# ETHERNET.net
KiCad netlist of a schematic drawn in Altium Designer
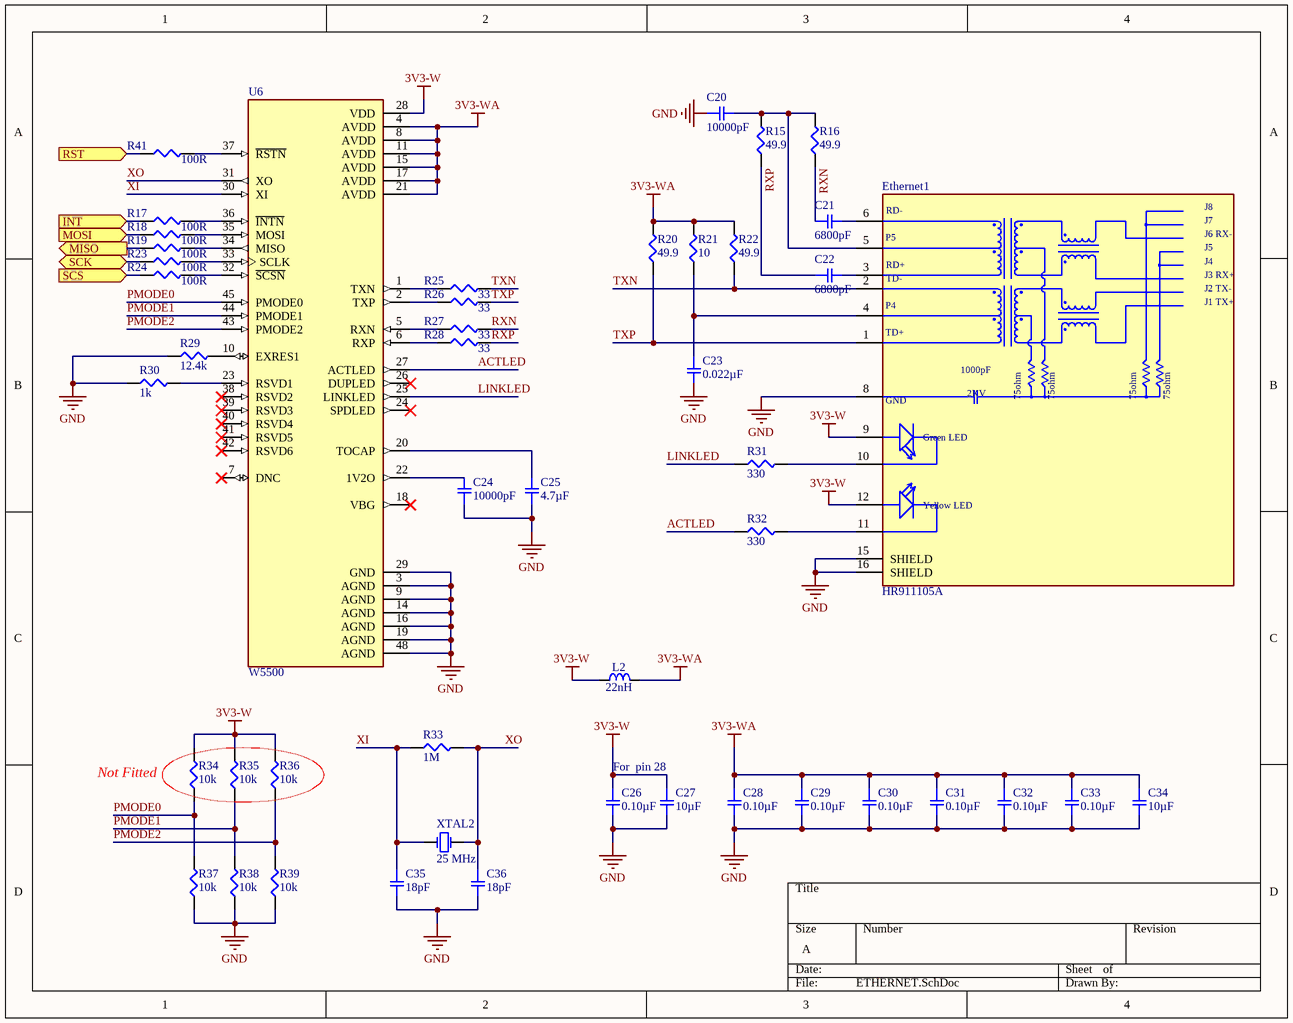
[diagram p0: ETHERNET.SchDoc]

(export (version "E")
  (design (tool "Eeschema 10.0.6"))
  (components
    (comp (ref "C20")
      (value "10000pF")
      (footprint "0805")
      (description "CAP CER 10000PF 250V X7T 0805")
      (fields
        (field (name "DIGI-KEY PART NUMBER") "490-13986-1-ND")
        (field (name "PART NUMBER") "GC321AD72E103KX01D")
      )
      (libsource (lib "Cap_805") (part "GC321AD72E103KX01D"))
    )
    (comp (ref "C21")
      (value "6800pF")
      (footprint "0805")
      (description "CAP CER 6800PF 50V X7R 0805")
      (fields
        (field (name "DIGI-KEY PART NUMBER") "490-5853-1-ND")
        (field (name "PART NUMBER") "GCJ216R71H682KA01D")
      )
      (libsource (lib "Cap_805") (part "GCJ216R71H682KA01D"))
    )
    (comp (ref "C22")
      (value "6800pF")
      (footprint "0805")
      (description "CAP CER 6800PF 50V X7R 0805")
      (fields
        (field (name "DIGI-KEY PART NUMBER") "490-5853-1-ND")
        (field (name "PART NUMBER") "GCJ216R71H682KA01D")
      )
      (libsource (lib "Cap_805") (part "GCJ216R71H682KA01D"))
    )
    (comp (ref "C23")
      (value "0.022µF")
      (footprint "0805")
      (description "CAP CER 0.022UF 50V X7R 0805")
      (fields
        (field (name "DIGI-KEY PART NUMBER") "490-5842-1-ND")
        (field (name "PART NUMBER") "GCJ216R71H223KA01D")
      )
      (libsource (lib "Cap_805") (part "GCJ216R71H223KA01D"))
    )
    (comp (ref "C24")
      (value "10000pF")
      (footprint "0805")
      (description "CAP CER 10000PF 250V X7T 0805")
      (fields
        (field (name "DIGI-KEY PART NUMBER") "490-13986-1-ND")
        (field (name "PART NUMBER") "GC321AD72E103KX01D")
      )
      (libsource (lib "Cap_805") (part "GC321AD72E103KX01D"))
    )
    (comp (ref "C25")
      (value "4.7µF")
      (footprint "0805")
      (description "CAP CER 4.7UF 10V X7S 0805")
      (fields
        (field (name "DIGI-KEY PART NUMBER") "490-6062-1-ND")
        (field (name "PART NUMBER") "GCM21BC71A475KA73L")
      )
      (libsource (lib "Cap_805") (part "GCM21BC71A475KA73L"))
    )
    (comp (ref "C26")
      (value "0.10µF")
      (footprint "0805")
      (description "CAP CER 0.1UF 25V X7R 0805")
      (fields
        (field (name "DIGI-KEY PART NUMBER") "490-12754-1-ND")
        (field (name "PART NUMBER") "GRM219R71E104KA01D")
      )
      (libsource (lib "Cap_805") (part "GRM219R71E104KA01D"))
    )
    (comp (ref "C27")
      (value "10µF")
      (footprint "0805")
      (description "CAP CER 10UF 10V X7R 0805")
      (fields
        (field (name "DIGI-KEY PART NUMBER") "490-12646-1-ND")
        (field (name "PART NUMBER") "GCJ21BR71A106KE01L")
      )
      (libsource (lib "Cap_805") (part "GCJ21BR71A106KE01L"))
    )
    (comp (ref "C28")
      (value "0.10µF")
      (footprint "0805")
      (description "CAP CER 0.1UF 25V X7R 0805")
      (fields
        (field (name "DIGI-KEY PART NUMBER") "490-12754-1-ND")
        (field (name "PART NUMBER") "GRM219R71E104KA01D")
      )
      (libsource (lib "Cap_805") (part "GRM219R71E104KA01D"))
    )
    (comp (ref "C29")
      (value "0.10µF")
      (footprint "0805")
      (description "CAP CER 0.1UF 25V X7R 0805")
      (fields
        (field (name "DIGI-KEY PART NUMBER") "490-12754-1-ND")
        (field (name "PART NUMBER") "GRM219R71E104KA01D")
      )
      (libsource (lib "Cap_805") (part "GRM219R71E104KA01D"))
    )
    (comp (ref "C30")
      (value "0.10µF")
      (footprint "0805")
      (description "CAP CER 0.1UF 25V X7R 0805")
      (fields
        (field (name "DIGI-KEY PART NUMBER") "490-12754-1-ND")
        (field (name "PART NUMBER") "GRM219R71E104KA01D")
      )
      (libsource (lib "Cap_805") (part "GRM219R71E104KA01D"))
    )
    (comp (ref "C31")
      (value "0.10µF")
      (footprint "0805")
      (description "CAP CER 0.1UF 25V X7R 0805")
      (fields
        (field (name "DIGI-KEY PART NUMBER") "490-12754-1-ND")
        (field (name "PART NUMBER") "GRM219R71E104KA01D")
      )
      (libsource (lib "Cap_805") (part "GRM219R71E104KA01D"))
    )
    (comp (ref "C32")
      (value "0.10µF")
      (footprint "0805")
      (description "CAP CER 0.1UF 25V X7R 0805")
      (fields
        (field (name "DIGI-KEY PART NUMBER") "490-12754-1-ND")
        (field (name "PART NUMBER") "GRM219R71E104KA01D")
      )
      (libsource (lib "Cap_805") (part "GRM219R71E104KA01D"))
    )
    (comp (ref "C33")
      (value "0.10µF")
      (footprint "0805")
      (description "CAP CER 0.1UF 25V X7R 0805")
      (fields
        (field (name "DIGI-KEY PART NUMBER") "490-12754-1-ND")
        (field (name "PART NUMBER") "GRM219R71E104KA01D")
      )
      (libsource (lib "Cap_805") (part "GRM219R71E104KA01D"))
    )
    (comp (ref "C34")
      (value "10µF")
      (footprint "0805")
      (description "CAP CER 10UF 10V X7R 0805")
      (fields
        (field (name "DIGI-KEY PART NUMBER") "490-12646-1-ND")
        (field (name "PART NUMBER") "GCJ21BR71A106KE01L")
      )
      (libsource (lib "Cap_805") (part "GCJ21BR71A106KE01L"))
    )
    (comp (ref "C35")
      (value "18pF")
      (footprint "0805")
      (description "CAP CER 18PF 100V NP0 0805")
      (fields
        (field (name "DIGI-KEY PART NUMBER") "490-3606-1-ND")
        (field (name "PART NUMBER") "GQM2195C2A180JB01D")
      )
      (libsource (lib "Cap_805") (part "GQM2195C2A180JB01D"))
    )
    (comp (ref "C36")
      (value "18pF")
      (footprint "0805")
      (description "CAP CER 18PF 100V NP0 0805")
      (fields
        (field (name "DIGI-KEY PART NUMBER") "490-3606-1-ND")
        (field (name "PART NUMBER") "GQM2195C2A180JB01D")
      )
      (libsource (lib "Cap_805") (part "GQM2195C2A180JB01D"))
    )
    (comp (ref "Ethernet1")
      (value "HR911105A")
      (footprint "HANRUN_HR911105A")
      (description "HR911105A Ethernet Interface Arduino Platform Evaluation Expansion Board")
      (fields (field (name "MF") "DFRobot"))
      (libsource (lib "RJ45 Ethernet Connector HR911105A") (part "HR911105A"))
    )
    (comp (ref "L2")
      (value "22nH")
      (footprint "0805")
      (description "Inductor")
      (fields
        (field (name "PART NUMBER") "IND0805_WURTH_742792022")
        (field (name "POWER") "2A")
        (field (name "AUTHOR") "CERN DEM JLC")
      )
      (libsource (lib "Inductors SMD") (part "IND0805_WURTH_742792022"))
    )
    (comp (ref "R15")
      (value "49.9")
      (footprint "0805")
      (description "RES SMD 49.9 OHM 1% 1/8W 0805")
      (fields
        (field (name "PART NUMBER") "ERJ-6ENF49R9V")
        (field (name "DIGI-KEY PART NUMBER") "P49.9CCT-ND")
      )
      (libsource (lib "Res_805") (part "ERJ-6ENF49R9V"))
    )
    (comp (ref "R16")
      (value "49.9")
      (footprint "0805")
      (description "RES SMD 49.9 OHM 1% 1/8W 0805")
      (fields
        (field (name "PART NUMBER") "ERJ-6ENF49R9V")
        (field (name "DIGI-KEY PART NUMBER") "P49.9CCT-ND")
      )
      (libsource (lib "Res_805") (part "ERJ-6ENF49R9V"))
    )
    (comp (ref "R17")
      (value "100R")
      (footprint "0805")
      (description "RES SMD 33 OHM 1% 1/8W 0805")
      (fields
        (field (name "PART NUMBER") "ERJ-6ENF33R0V")
        (field (name "DIGI-KEY PART NUMBER") "P33.0CCT-ND")
      )
      (libsource (lib "Res_805") (part "ERJ-6ENF33R0V"))
    )
    (comp (ref "R18")
      (value "100R")
      (footprint "0805")
      (description "RES SMD 33 OHM 1% 1/8W 0805")
      (fields
        (field (name "PART NUMBER") "ERJ-6ENF33R0V")
        (field (name "DIGI-KEY PART NUMBER") "P33.0CCT-ND")
      )
      (libsource (lib "Res_805") (part "ERJ-6ENF33R0V"))
    )
    (comp (ref "R19")
      (value "100R")
      (footprint "0805")
      (description "RES SMD 33 OHM 1% 1/8W 0805")
      (fields
        (field (name "PART NUMBER") "ERJ-6ENF33R0V")
        (field (name "DIGI-KEY PART NUMBER") "P33.0CCT-ND")
      )
      (libsource (lib "Res_805") (part "ERJ-6ENF33R0V"))
    )
    (comp (ref "R20")
      (value "49.9")
      (footprint "0805")
      (description "RES SMD 49.9 OHM 1% 1/8W 0805")
      (fields
        (field (name "PART NUMBER") "ERJ-6ENF49R9V")
        (field (name "DIGI-KEY PART NUMBER") "P49.9CCT-ND")
      )
      (libsource (lib "Res_805") (part "ERJ-6ENF49R9V"))
    )
    (comp (ref "R21")
      (value "10")
      (footprint "0805")
      (description "RES SMD 10 OHM 1% 1/8W 0805")
      (fields
        (field (name "PART NUMBER") "ERJ-6ENF10R0V")
        (field (name "DIGI-KEY PART NUMBER") "P10.0CCT-ND")
      )
      (libsource (lib "Res_805") (part "ERJ-6ENF10R0V"))
    )
    (comp (ref "R22")
      (value "49.9")
      (footprint "0805")
      (description "RES SMD 49.9 OHM 1% 1/8W 0805")
      (fields
        (field (name "PART NUMBER") "ERJ-6ENF49R9V")
        (field (name "DIGI-KEY PART NUMBER") "P49.9CCT-ND")
      )
      (libsource (lib "Res_805") (part "ERJ-6ENF49R9V"))
    )
    (comp (ref "R23")
      (value "100R")
      (footprint "0805")
      (description "RES SMD 33 OHM 1% 1/8W 0805")
      (fields
        (field (name "PART NUMBER") "ERJ-6ENF33R0V")
        (field (name "DIGI-KEY PART NUMBER") "P33.0CCT-ND")
      )
      (libsource (lib "Res_805") (part "ERJ-6ENF33R0V"))
    )
    (comp (ref "R24")
      (value "100R")
      (footprint "0805")
      (description "RES SMD 33 OHM 1% 1/8W 0805")
      (fields
        (field (name "PART NUMBER") "ERJ-6ENF33R0V")
        (field (name "DIGI-KEY PART NUMBER") "P33.0CCT-ND")
      )
      (libsource (lib "Res_805") (part "ERJ-6ENF33R0V"))
    )
    (comp (ref "R25")
      (value "33")
      (footprint "0805")
      (description "RES SMD 33 OHM 1% 1/8W 0805")
      (fields
        (field (name "PART NUMBER") "ERJ-6ENF33R0V")
        (field (name "DIGI-KEY PART NUMBER") "P33.0CCT-ND")
      )
      (libsource (lib "Res_805") (part "ERJ-6ENF33R0V"))
    )
    (comp (ref "R26")
      (value "33")
      (footprint "0805")
      (description "RES SMD 33 OHM 1% 1/8W 0805")
      (fields
        (field (name "PART NUMBER") "ERJ-6ENF33R0V")
        (field (name "DIGI-KEY PART NUMBER") "P33.0CCT-ND")
      )
      (libsource (lib "Res_805") (part "ERJ-6ENF33R0V"))
    )
    (comp (ref "R27")
      (value "33")
      (footprint "0805")
      (description "RES SMD 33 OHM 1% 1/8W 0805")
      (fields
        (field (name "PART NUMBER") "ERJ-6ENF33R0V")
        (field (name "DIGI-KEY PART NUMBER") "P33.0CCT-ND")
      )
      (libsource (lib "Res_805") (part "ERJ-6ENF33R0V"))
    )
    (comp (ref "R28")
      (value "33")
      (footprint "0805")
      (description "RES SMD 33 OHM 1% 1/8W 0805")
      (fields
        (field (name "PART NUMBER") "ERJ-6ENF33R0V")
        (field (name "DIGI-KEY PART NUMBER") "P33.0CCT-ND")
      )
      (libsource (lib "Res_805") (part "ERJ-6ENF33R0V"))
    )
    (comp (ref "R29")
      (value "12.4k")
      (footprint "0805")
      (description "RES SMD 12.4K OHM 1% 1/8W 0805")
      (fields
        (field (name "PART NUMBER") "ERJ-6ENF1242V")
        (field (name "DIGI-KEY PART NUMBER") "P12.4KCCT-ND")
      )
      (libsource (lib "Res_805") (part "ERJ-6ENF1242V"))
    )
    (comp (ref "R30")
      (value "1k")
      (footprint "0805")
      (description "RES SMD 1K OHM 1% 1/8W 0805")
      (fields
        (field (name "PART NUMBER") "ERJ-6ENF1001V")
        (field (name "DIGI-KEY PART NUMBER") "P1.00KCCT-ND")
      )
      (libsource (lib "Res_805") (part "ERJ-6ENF1001V"))
    )
    (comp (ref "R31")
      (value "330")
      (footprint "0805")
      (description "RES SMD 330 OHM 5% 1/8W 0805")
      (fields (field (name "PART NUMBER") "ERJ-6GEYJ331V") (field (name "DIGI-KEY PART NUMBER") "P330ACT-ND"))
      (libsource (lib "Res_805") (part "ERJ-6GEYJ331V"))
    )
    (comp (ref "R32")
      (value "330")
      (footprint "0805")
      (description "RES SMD 330 OHM 5% 1/8W 0805")
      (fields (field (name "PART NUMBER") "ERJ-6GEYJ331V") (field (name "DIGI-KEY PART NUMBER") "P330ACT-ND"))
      (libsource (lib "Res_805") (part "ERJ-6GEYJ331V"))
    )
    (comp (ref "R33")
      (value "1M")
      (footprint "0805")
      (description "RES SMD 1M OHM 1% 1/8W 0805")
      (fields
        (field (name "PART NUMBER") "ERJ-6ENF1004V")
        (field (name "DIGI-KEY PART NUMBER") "P1.00MCCT-ND")
      )
      (libsource (lib "Res_805") (part "ERJ-6ENF1004V"))
    )
    (comp (ref "R34")
      (value "10k")
      (footprint "0805")
      (description "RES SMD 10K OHM 1% 1/8W 0805")
      (fields
        (field (name "PART NUMBER") "ERJ-6ENF1002V")
        (field (name "DIGI-KEY PART NUMBER") "P10.0KCCT-ND")
      )
      (libsource (lib "Res_805") (part "ERJ-6ENF1002V"))
    )
    (comp (ref "R35")
      (value "10k")
      (footprint "0805")
      (description "RES SMD 10K OHM 1% 1/8W 0805")
      (fields
        (field (name "PART NUMBER") "ERJ-6ENF1002V")
        (field (name "DIGI-KEY PART NUMBER") "P10.0KCCT-ND")
      )
      (libsource (lib "Res_805") (part "ERJ-6ENF1002V"))
    )
    (comp (ref "R36")
      (value "10k")
      (footprint "0805")
      (description "RES SMD 10K OHM 1% 1/8W 0805")
      (fields
        (field (name "PART NUMBER") "ERJ-6ENF1002V")
        (field (name "DIGI-KEY PART NUMBER") "P10.0KCCT-ND")
      )
      (libsource (lib "Res_805") (part "ERJ-6ENF1002V"))
    )
    (comp (ref "R37")
      (value "10k")
      (footprint "0805")
      (description "RES SMD 10K OHM 1% 1/8W 0805")
      (fields
        (field (name "PART NUMBER") "ERJ-6ENF1002V")
        (field (name "DIGI-KEY PART NUMBER") "P10.0KCCT-ND")
      )
      (libsource (lib "Res_805") (part "ERJ-6ENF1002V"))
    )
    (comp (ref "R38")
      (value "10k")
      (footprint "0805")
      (description "RES SMD 10K OHM 1% 1/8W 0805")
      (fields
        (field (name "PART NUMBER") "ERJ-6ENF1002V")
        (field (name "DIGI-KEY PART NUMBER") "P10.0KCCT-ND")
      )
      (libsource (lib "Res_805") (part "ERJ-6ENF1002V"))
    )
    (comp (ref "R39")
      (value "10k")
      (footprint "0805")
      (description "RES SMD 10K OHM 1% 1/8W 0805")
      (fields
        (field (name "PART NUMBER") "ERJ-6ENF1002V")
        (field (name "DIGI-KEY PART NUMBER") "P10.0KCCT-ND")
      )
      (libsource (lib "Res_805") (part "ERJ-6ENF1002V"))
    )
    (comp (ref "R41")
      (value "100R")
      (footprint "0805")
      (description "RES SMD 33 OHM 1% 1/8W 0805")
      (fields
        (field (name "PART NUMBER") "ERJ-6ENF33R0V")
        (field (name "DIGI-KEY PART NUMBER") "P33.0CCT-ND")
      )
      (libsource (lib "Res_805") (part "ERJ-6ENF33R0V"))
    )
    (comp (ref "U6")
      (value "W5500")
      (footprint "QFP50P900X900X160-48N")
      (description "Socket Contact Silver 17-20 AWG Crimp Power")
      (fields (field (name "MF") "WIZnet"))
      (libsource (lib "Wiznet - W5500") (part "W5500"))
    )
    (comp (ref "XTAL2")
      (value "25 MHz")
      (footprint "CRYSTAL Small")
      (description "XTAL Crystal")
      (fields (field (name "DESIGNER") "ABBAS BASEREH"))
      (libsource (lib "Altium") (part "XTAL"))
    )
  )
  (nets
    (net (code "1") (name "/ACTLED") (class "Default")
      (node (ref "R32") (pin "1") (pinfunction "1_1") (pintype "passive"))
      (node (ref "U6") (pin "27") (pinfunction "ACTLED_27") (pintype "output"))
    )
    (net (code "2") (name "/INT") (class "Default")
      (node (ref "R17") (pin "1") (pinfunction "1_1") (pintype "passive"))
    )
    (net (code "3") (name "/LINKLED") (class "Default")
      (node (ref "R31") (pin "1") (pinfunction "1_1") (pintype "passive"))
      (node (ref "U6") (pin "25") (pinfunction "LINKLED_25") (pintype "output"))
    )
    (net (code "4") (name "/MISO") (class "Default")
      (node (ref "R19") (pin "1") (pinfunction "1_1") (pintype "passive"))
    )
    (net (code "5") (name "/MOSI") (class "Default")
      (node (ref "R18") (pin "1") (pinfunction "1_1") (pintype "passive"))
    )
    (net (code "6") (name "/PMODE0") (class "Default")
      (node (ref "R34") (pin "1") (pinfunction "1_1") (pintype "passive"))
      (node (ref "R37") (pin "2") (pinfunction "2_2") (pintype "passive"))
      (node (ref "U6") (pin "45") (pinfunction "PMODE0_45") (pintype "input"))
    )
    (net (code "7") (name "/PMODE1") (class "Default")
      (node (ref "R35") (pin "1") (pinfunction "1_1") (pintype "passive"))
      (node (ref "R38") (pin "2") (pinfunction "2_2") (pintype "passive"))
      (node (ref "U6") (pin "44") (pinfunction "PMODE1_44") (pintype "input"))
    )
    (net (code "8") (name "/PMODE2") (class "Default")
      (node (ref "R36") (pin "1") (pinfunction "1_1") (pintype "passive"))
      (node (ref "R39") (pin "2") (pinfunction "2_2") (pintype "passive"))
      (node (ref "U6") (pin "43") (pinfunction "PMODE2_43") (pintype "input"))
    )
    (net (code "9") (name "/RST") (class "Default")
      (node (ref "R41") (pin "1") (pinfunction "1_1") (pintype "passive"))
    )
    (net (code "10") (name "/RXN") (class "Default")
      (node (ref "C21") (pin "1") (pinfunction "1_1") (pintype "passive"))
      (node (ref "R16") (pin "1") (pinfunction "1_1") (pintype "passive"))
      (node (ref "R27") (pin "2") (pinfunction "2_2") (pintype "passive"))
    )
    (net (code "11") (name "/RXP") (class "Default")
      (node (ref "C22") (pin "1") (pinfunction "1_1") (pintype "passive"))
      (node (ref "R15") (pin "1") (pinfunction "1_1") (pintype "passive"))
      (node (ref "R28") (pin "2") (pinfunction "2_2") (pintype "passive"))
    )
    (net (code "12") (name "/SCK") (class "Default")
      (node (ref "R23") (pin "1") (pinfunction "1_1") (pintype "passive"))
    )
    (net (code "13") (name "/SCS") (class "Default")
      (node (ref "R24") (pin "1") (pinfunction "1_1") (pintype "passive"))
    )
    (net (code "14") (name "/TXN") (class "Default")
      (node (ref "Ethernet1") (pin "2") (pinfunction "TD-_2") (pintype "passive"))
      (node (ref "R22") (pin "1") (pinfunction "1_1") (pintype "passive"))
      (node (ref "R25") (pin "2") (pinfunction "2_2") (pintype "passive"))
    )
    (net (code "15") (name "/TXP") (class "Default")
      (node (ref "Ethernet1") (pin "1") (pinfunction "TD+_1") (pintype "passive"))
      (node (ref "R20") (pin "1") (pinfunction "1_1") (pintype "passive"))
      (node (ref "R26") (pin "2") (pinfunction "2_2") (pintype "passive"))
    )
    (net (code "16") (name "/XI") (class "Default")
      (node (ref "C35") (pin "1") (pinfunction "1_1") (pintype "passive"))
      (node (ref "R33") (pin "1") (pinfunction "1_1") (pintype "passive"))
      (node (ref "U6") (pin "30") (pinfunction "XI_30") (pintype "input"))
      (node (ref "XTAL2") (pin "2") (pinfunction "OSC2_2") (pintype "passive"))
    )
    (net (code "17") (name "/XO") (class "Default")
      (node (ref "C36") (pin "1") (pinfunction "1_1") (pintype "passive"))
      (node (ref "R33") (pin "2") (pinfunction "2_2") (pintype "passive"))
      (node (ref "U6") (pin "31") (pinfunction "XO_31") (pintype "output"))
      (node (ref "XTAL2") (pin "1") (pinfunction "OSC1_1") (pintype "passive"))
    )
    (net (code "18") (name "3V3-W") (class "Default")
      (node (ref "C26") (pin "1") (pinfunction "1_1") (pintype "passive"))
      (node (ref "C27") (pin "1") (pinfunction "1_1") (pintype "passive"))
      (node (ref "Ethernet1") (pin "12") (pinfunction "YA_12") (pintype "passive"))
      (node (ref "Ethernet1") (pin "9") (pinfunction "GA_9") (pintype "passive"))
      (node (ref "L2") (pin "1") (pinfunction "1_1") (pintype "passive"))
      (node (ref "R34") (pin "2") (pinfunction "2_2") (pintype "passive"))
      (node (ref "R35") (pin "2") (pinfunction "2_2") (pintype "passive"))
      (node (ref "R36") (pin "2") (pinfunction "2_2") (pintype "passive"))
      (node (ref "U6") (pin "28") (pinfunction "VDD_28") (pintype "power_in"))
    )
    (net (code "19") (name "3V3-WA") (class "Default")
      (node (ref "C28") (pin "1") (pinfunction "1_1") (pintype "passive"))
      (node (ref "C29") (pin "1") (pinfunction "1_1") (pintype "passive"))
      (node (ref "C30") (pin "1") (pinfunction "1_1") (pintype "passive"))
      (node (ref "C31") (pin "1") (pinfunction "1_1") (pintype "passive"))
      (node (ref "C32") (pin "1") (pinfunction "1_1") (pintype "passive"))
      (node (ref "C33") (pin "1") (pinfunction "1_1") (pintype "passive"))
      (node (ref "C34") (pin "1") (pinfunction "1_1") (pintype "passive"))
      (node (ref "L2") (pin "2") (pinfunction "2_2") (pintype "passive"))
      (node (ref "R20") (pin "2") (pinfunction "2_2") (pintype "passive"))
      (node (ref "R21") (pin "2") (pinfunction "2_2") (pintype "passive"))
      (node (ref "R22") (pin "2") (pinfunction "2_2") (pintype "passive"))
      (node (ref "U6") (pin "11") (pinfunction "AVDD_11") (pintype "power_in"))
      (node (ref "U6") (pin "15") (pinfunction "AVDD_15") (pintype "power_in"))
      (node (ref "U6") (pin "17") (pinfunction "AVDD_17") (pintype "power_in"))
      (node (ref "U6") (pin "21") (pinfunction "AVDD_21") (pintype "power_in"))
      (node (ref "U6") (pin "4") (pinfunction "AVDD_4") (pintype "power_in"))
      (node (ref "U6") (pin "8") (pinfunction "AVDD_8") (pintype "power_in"))
    )
    (net (code "20") (name "GND") (class "Default")
      (node (ref "C20") (pin "1") (pinfunction "1_1") (pintype "passive"))
      (node (ref "C23") (pin "2") (pinfunction "2_2") (pintype "passive"))
      (node (ref "C24") (pin "1") (pinfunction "1_1") (pintype "passive"))
      (node (ref "C25") (pin "1") (pinfunction "1_1") (pintype "passive"))
      (node (ref "C26") (pin "2") (pinfunction "2_2") (pintype "passive"))
      (node (ref "C27") (pin "2") (pinfunction "2_2") (pintype "passive"))
      (node (ref "C28") (pin "2") (pinfunction "2_2") (pintype "passive"))
      (node (ref "C29") (pin "2") (pinfunction "2_2") (pintype "passive"))
      (node (ref "C30") (pin "2") (pinfunction "2_2") (pintype "passive"))
      (node (ref "C31") (pin "2") (pinfunction "2_2") (pintype "passive"))
      (node (ref "C32") (pin "2") (pinfunction "2_2") (pintype "passive"))
      (node (ref "C33") (pin "2") (pinfunction "2_2") (pintype "passive"))
      (node (ref "C34") (pin "2") (pinfunction "2_2") (pintype "passive"))
      (node (ref "C35") (pin "2") (pinfunction "2_2") (pintype "passive"))
      (node (ref "C36") (pin "2") (pinfunction "2_2") (pintype "passive"))
      (node (ref "Ethernet1") (pin "15") (pinfunction "SHIELD_15") (pintype "passive"))
      (node (ref "Ethernet1") (pin "16") (pinfunction "SHIELD_16") (pintype "passive"))
      (node (ref "Ethernet1") (pin "8") (pinfunction "GND_8") (pintype "power_in"))
      (node (ref "R29") (pin "1") (pinfunction "1_1") (pintype "passive"))
      (node (ref "R30") (pin "1") (pinfunction "1_1") (pintype "passive"))
      (node (ref "R37") (pin "1") (pinfunction "1_1") (pintype "passive"))
      (node (ref "R38") (pin "1") (pinfunction "1_1") (pintype "passive"))
      (node (ref "R39") (pin "1") (pinfunction "1_1") (pintype "passive"))
      (node (ref "U6") (pin "14") (pinfunction "AGND_14") (pintype "power_in"))
      (node (ref "U6") (pin "16") (pinfunction "AGND_16") (pintype "power_in"))
      (node (ref "U6") (pin "19") (pinfunction "AGND_19") (pintype "power_in"))
      (node (ref "U6") (pin "29") (pinfunction "GND_29") (pintype "passive"))
      (node (ref "U6") (pin "3") (pinfunction "AGND_3") (pintype "power_in"))
      (node (ref "U6") (pin "48") (pinfunction "AGND_48") (pintype "power_in"))
      (node (ref "U6") (pin "9") (pinfunction "AGND_9") (pintype "power_in"))
    )
    (net (code "21") (name "Net-(Ethernet1-GC)") (class "Default")
      (node (ref "Ethernet1") (pin "10") (pinfunction "GC_10") (pintype "passive"))
      (node (ref "R31") (pin "2") (pinfunction "2_2") (pintype "passive"))
    )
    (net (code "22") (name "Net-(Ethernet1-P4)") (class "Default")
      (node (ref "C23") (pin "1") (pinfunction "1_1") (pintype "passive"))
      (node (ref "Ethernet1") (pin "4") (pinfunction "P4_4") (pintype "passive"))
      (node (ref "R21") (pin "1") (pinfunction "1_1") (pintype "passive"))
    )
    (net (code "23") (name "Net-(Ethernet1-P5)") (class "Default")
      (node (ref "C20") (pin "2") (pinfunction "2_2") (pintype "passive"))
      (node (ref "Ethernet1") (pin "5") (pinfunction "P5_5") (pintype "passive"))
      (node (ref "R15") (pin "2") (pinfunction "2_2") (pintype "passive"))
      (node (ref "R16") (pin "2") (pinfunction "2_2") (pintype "passive"))
    )
    (net (code "24") (name "Net-(Ethernet1-RD+)") (class "Default")
      (node (ref "C22") (pin "2") (pinfunction "2_2") (pintype "passive"))
      (node (ref "Ethernet1") (pin "3") (pinfunction "RD+_3") (pintype "passive"))
    )
    (net (code "25") (name "Net-(Ethernet1-RD-)") (class "Default")
      (node (ref "C21") (pin "2") (pinfunction "2_2") (pintype "passive"))
      (node (ref "Ethernet1") (pin "6") (pinfunction "RD-_6") (pintype "passive"))
    )
    (net (code "26") (name "Net-(Ethernet1-YC)") (class "Default")
      (node (ref "Ethernet1") (pin "11") (pinfunction "YC_11") (pintype "passive"))
      (node (ref "R32") (pin "2") (pinfunction "2_2") (pintype "passive"))
    )
    (net (code "27") (name "Net-(U6-1V2O)") (class "Default")
      (node (ref "C24") (pin "2") (pinfunction "2_2") (pintype "passive"))
      (node (ref "U6") (pin "22") (pinfunction "1V2O_22") (pintype "output"))
    )
    (net (code "28") (name "Net-(U6-EXRES1)") (class "Default")
      (node (ref "R29") (pin "2") (pinfunction "2_2") (pintype "passive"))
      (node (ref "U6") (pin "10") (pinfunction "EXRES1_10") (pintype "bidirectional"))
    )
    (net (code "29") (name "Net-(U6-MISO)") (class "Default")
      (node (ref "R19") (pin "2") (pinfunction "2_2") (pintype "passive"))
      (node (ref "U6") (pin "34") (pinfunction "MISO_34") (pintype "output"))
    )
    (net (code "30") (name "Net-(U6-MOSI)") (class "Default")
      (node (ref "R18") (pin "2") (pinfunction "2_2") (pintype "passive"))
      (node (ref "U6") (pin "35") (pinfunction "MOSI_35") (pintype "input"))
    )
    (net (code "31") (name "Net-(U6-RSVD1)") (class "Default")
      (node (ref "R30") (pin "2") (pinfunction "2_2") (pintype "passive"))
      (node (ref "U6") (pin "23") (pinfunction "RSVD1_23") (pintype "input"))
    )
    (net (code "32") (name "Net-(U6-RXN)") (class "Default")
      (node (ref "R27") (pin "1") (pinfunction "1_1") (pintype "passive"))
      (node (ref "U6") (pin "5") (pinfunction "RXN_5") (pintype "input"))
    )
    (net (code "33") (name "Net-(U6-RXP)") (class "Default")
      (node (ref "R28") (pin "1") (pinfunction "1_1") (pintype "passive"))
      (node (ref "U6") (pin "6") (pinfunction "RXP_6") (pintype "input"))
    )
    (net (code "34") (name "Net-(U6-SCLK)") (class "Default")
      (node (ref "R23") (pin "2") (pinfunction "2_2") (pintype "passive"))
      (node (ref "U6") (pin "33") (pinfunction "SCLK_33") (pintype "input"))
    )
    (net (code "35") (name "Net-(U6-TOCAP)") (class "Default")
      (node (ref "C25") (pin "2") (pinfunction "2_2") (pintype "passive"))
      (node (ref "U6") (pin "20") (pinfunction "TOCAP_20") (pintype "output"))
    )
    (net (code "36") (name "Net-(U6-TXN)") (class "Default")
      (node (ref "R25") (pin "1") (pinfunction "1_1") (pintype "passive"))
      (node (ref "U6") (pin "1") (pinfunction "TXN_1") (pintype "output"))
    )
    (net (code "37") (name "Net-(U6-TXP)") (class "Default")
      (node (ref "R26") (pin "1") (pinfunction "1_1") (pintype "passive"))
      (node (ref "U6") (pin "2") (pinfunction "TXP_2") (pintype "output"))
    )
    (net (code "38") (name "Net-(U6-~{INTN})") (class "Default")
      (node (ref "R17") (pin "2") (pinfunction "2_2") (pintype "passive"))
      (node (ref "U6") (pin "36") (pinfunction "~{INTN}_36") (pintype "input"))
    )
    (net (code "39") (name "Net-(U6-~{RSTN})") (class "Default")
      (node (ref "R41") (pin "2") (pinfunction "2_2") (pintype "passive"))
      (node (ref "U6") (pin "37") (pinfunction "~{RSTN}_37") (pintype "input"))
    )
    (net (code "40") (name "Net-(U6-~{SCSN})") (class "Default")
      (node (ref "R24") (pin "2") (pinfunction "2_2") (pintype "passive"))
      (node (ref "U6") (pin "32") (pinfunction "~{SCSN}_32") (pintype "input"))
    )
    (net (code "41") (name "unconnected-(U6-DNC-Pad7)") (class "Default")
      (node (ref "U6") (pin "7") (pinfunction "DNC_7") (pintype "bidirectional+no_connect"))
    )
    (net (code "42") (name "unconnected-(U6-DUPLED-Pad26)") (class "Default")
      (node (ref "U6") (pin "26") (pinfunction "DUPLED_26") (pintype "output+no_connect"))
    )
    (net (code "43") (name "unconnected-(U6-RSVD2-Pad38)") (class "Default")
      (node (ref "U6") (pin "38") (pinfunction "RSVD2_38") (pintype "input+no_connect"))
    )
    (net (code "44") (name "unconnected-(U6-RSVD3-Pad39)") (class "Default")
      (node (ref "U6") (pin "39") (pinfunction "RSVD3_39") (pintype "input+no_connect"))
    )
    (net (code "45") (name "unconnected-(U6-RSVD4-Pad40)") (class "Default")
      (node (ref "U6") (pin "40") (pinfunction "RSVD4_40") (pintype "input+no_connect"))
    )
    (net (code "46") (name "unconnected-(U6-RSVD5-Pad41)") (class "Default")
      (node (ref "U6") (pin "41") (pinfunction "RSVD5_41") (pintype "input+no_connect"))
    )
    (net (code "47") (name "unconnected-(U6-RSVD6-Pad42)") (class "Default")
      (node (ref "U6") (pin "42") (pinfunction "RSVD6_42") (pintype "input+no_connect"))
    )
    (net (code "48") (name "unconnected-(U6-SPDLED-Pad24)") (class "Default")
      (node (ref "U6") (pin "24") (pinfunction "SPDLED_24") (pintype "output+no_connect"))
    )
    (net (code "49") (name "unconnected-(U6-VBG-Pad18)") (class "Default")
      (node (ref "U6") (pin "18") (pinfunction "VBG_18") (pintype "output+no_connect"))
    )
  )
)
